# untitled.net
KiCad netlist of a schematic drawn in EAGLE
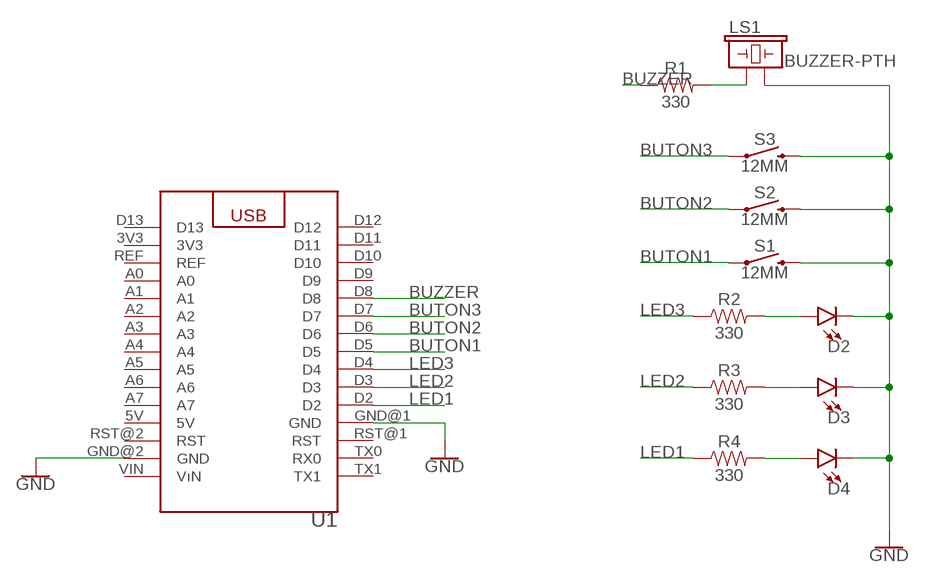
[diagram p0: schematic, sheet 1]

(export (version "E")
  (design (tool "Eeschema 10.0.6"))
  (components
    (comp (ref "D2")
      (value "LED-3MM-NO_SILK")
      (footprint "eagle-import:LED_3MM-NS")
      (libsource (lib "eagle-import") (part "LED-3MM-NO_SILK"))
    )
    (comp (ref "D3")
      (value "LED-3MM-NO_SILK")
      (footprint "eagle-import:LED_3MM-NS")
      (libsource (lib "eagle-import") (part "LED-3MM-NO_SILK"))
    )
    (comp (ref "D4")
      (value "LED-3MM-NO_SILK")
      (footprint "eagle-import:LED_3MM-NS")
      (libsource (lib "eagle-import") (part "LED-3MM-NO_SILK"))
    )
    (comp (ref "LS1")
      (value "BUZZER-PTH")
      (footprint "eagle-import:BUZZER-12MM")
      (libsource (lib "eagle-import") (part "BUZZER-PTH"))
    )
    (comp (ref "R1")
      (value "330")
      (footprint "eagle-import:AXIAL-0.3")
      (libsource (lib "eagle-import") (part "1KOHM-HORIZ-1/4W-5%"))
    )
    (comp (ref "R2")
      (value "330")
      (footprint "eagle-import:AXIAL-0.3")
      (libsource (lib "eagle-import") (part "1KOHM-HORIZ-1/4W-5%"))
    )
    (comp (ref "R3")
      (value "330")
      (footprint "eagle-import:AXIAL-0.3")
      (libsource (lib "eagle-import") (part "1KOHM-HORIZ-1/4W-5%"))
    )
    (comp (ref "R4")
      (value "330")
      (footprint "eagle-import:AXIAL-0.3")
      (libsource (lib "eagle-import") (part "1KOHM-HORIZ-1/4W-5%"))
    )
    (comp (ref "S1")
      (value "12MM")
      (footprint "eagle-import:TACTILE_SWITCH_PTH_12MM")
      (libsource (lib "eagle-import") (part "MOMENTARY-SWITCH-SPST-PTH-12MM"))
    )
    (comp (ref "S2")
      (value "12MM")
      (footprint "eagle-import:TACTILE_SWITCH_PTH_12MM")
      (libsource (lib "eagle-import") (part "MOMENTARY-SWITCH-SPST-PTH-12MM"))
    )
    (comp (ref "S3")
      (value "12MM")
      (footprint "eagle-import:TACTILE_SWITCH_PTH_12MM")
      (libsource (lib "eagle-import") (part "MOMENTARY-SWITCH-SPST-PTH-12MM"))
    )
    (comp (ref "U1")
      (value "ARDUINO_NANO")
      (footprint "eagle-import:ARDUINO_NANO")
      (libsource (lib "eagle-import") (part "ARDUINO_NANO"))
    )
  )
  (nets
    (net (code "1") (name "/BUTON1") (class "Default")
      (node (ref "S1") (pin "1") (pinfunction "1_1") (pintype "passive"))
      (node (ref "U1") (pin "D5") (pinfunction "D5_D5") (pintype "bidirectional"))
    )
    (net (code "2") (name "/BUTON2") (class "Default")
      (node (ref "S2") (pin "1") (pinfunction "1_1") (pintype "passive"))
      (node (ref "U1") (pin "D6") (pinfunction "D6_D6") (pintype "bidirectional"))
    )
    (net (code "3") (name "/BUTON3") (class "Default")
      (node (ref "S3") (pin "1") (pinfunction "1_1") (pintype "passive"))
      (node (ref "U1") (pin "D7") (pinfunction "D7_D7") (pintype "bidirectional"))
    )
    (net (code "4") (name "/BUZZER") (class "Default")
      (node (ref "R1") (pin "P$1") (pinfunction "1_P$1") (pintype "passive"))
      (node (ref "U1") (pin "D8") (pinfunction "D8_D8") (pintype "bidirectional"))
    )
    (net (code "5") (name "/LED1") (class "Default")
      (node (ref "R4") (pin "P$1") (pinfunction "1_P$1") (pintype "passive"))
      (node (ref "U1") (pin "D2") (pinfunction "D2_D2") (pintype "bidirectional"))
    )
    (net (code "6") (name "/LED2") (class "Default")
      (node (ref "R3") (pin "P$1") (pinfunction "1_P$1") (pintype "passive"))
      (node (ref "U1") (pin "D3") (pinfunction "D3_D3") (pintype "bidirectional"))
    )
    (net (code "7") (name "/LED3") (class "Default")
      (node (ref "R2") (pin "P$1") (pinfunction "1_P$1") (pintype "passive"))
      (node (ref "U1") (pin "D4") (pinfunction "D4_D4") (pintype "bidirectional"))
    )
    (net (code "8") (name "GND") (class "Default")
      (node (ref "D2") (pin "K") (pinfunction "C_K") (pintype "passive"))
      (node (ref "D3") (pin "K") (pinfunction "C_K") (pintype "passive"))
      (node (ref "D4") (pin "K") (pinfunction "C_K") (pintype "passive"))
      (node (ref "LS1") (pin "-") (pinfunction "2_-") (pintype "passive"))
      (node (ref "S1") (pin "3") (pinfunction "2_3") (pintype "passive"))
      (node (ref "S2") (pin "3") (pinfunction "2_3") (pintype "passive"))
      (node (ref "S3") (pin "3") (pinfunction "2_3") (pintype "passive"))
      (node (ref "U1") (pin "GND@1") (pinfunction "GND_GND@1") (pintype "bidirectional"))
      (node (ref "U1") (pin "GND@2") (pinfunction "GND_GND@2") (pintype "bidirectional"))
    )
    (net (code "9") (name "Net-(LS1-1)") (class "Default")
      (node (ref "LS1") (pin "+") (pinfunction "1_+") (pintype "passive"))
      (node (ref "R1") (pin "P$2") (pinfunction "2_P$2") (pintype "passive"))
    )
    (net (code "10") (name "Net-(R2-2)") (class "Default")
      (node (ref "D2") (pin "A") (pinfunction "A_A") (pintype "passive"))
      (node (ref "R2") (pin "P$2") (pinfunction "2_P$2") (pintype "passive"))
    )
    (net (code "11") (name "Net-(R3-2)") (class "Default")
      (node (ref "D3") (pin "A") (pinfunction "A_A") (pintype "passive"))
      (node (ref "R3") (pin "P$2") (pinfunction "2_P$2") (pintype "passive"))
    )
    (net (code "12") (name "Net-(R4-2)") (class "Default")
      (node (ref "D4") (pin "A") (pinfunction "A_A") (pintype "passive"))
      (node (ref "R4") (pin "P$2") (pinfunction "2_P$2") (pintype "passive"))
    )
    (net (code "13") (name "unconnected-(U1-Pad3V3)") (class "Default")
      (node (ref "U1") (pin "3V3") (pinfunction "3V3_3V3") (pintype "bidirectional"))
    )
    (net (code "14") (name "unconnected-(U1-Pad5V)") (class "Default")
      (node (ref "U1") (pin "5V") (pinfunction "5V_5V") (pintype "bidirectional"))
    )
    (net (code "15") (name "unconnected-(U1-PadA0)") (class "Default")
      (node (ref "U1") (pin "A0") (pinfunction "A0_A0") (pintype "bidirectional"))
    )
    (net (code "16") (name "unconnected-(U1-PadA1)") (class "Default")
      (node (ref "U1") (pin "A1") (pinfunction "A1_A1") (pintype "bidirectional"))
    )
    (net (code "17") (name "unconnected-(U1-PadA2)") (class "Default")
      (node (ref "U1") (pin "A2") (pinfunction "A2_A2") (pintype "bidirectional"))
    )
    (net (code "18") (name "unconnected-(U1-PadA3)") (class "Default")
      (node (ref "U1") (pin "A3") (pinfunction "A3_A3") (pintype "bidirectional"))
    )
    (net (code "19") (name "unconnected-(U1-PadA4)") (class "Default")
      (node (ref "U1") (pin "A4") (pinfunction "A4_A4") (pintype "bidirectional"))
    )
    (net (code "20") (name "unconnected-(U1-PadA5)") (class "Default")
      (node (ref "U1") (pin "A5") (pinfunction "A5_A5") (pintype "bidirectional"))
    )
    (net (code "21") (name "unconnected-(U1-PadA6)") (class "Default")
      (node (ref "U1") (pin "A6") (pinfunction "A6_A6") (pintype "bidirectional"))
    )
    (net (code "22") (name "unconnected-(U1-PadA7)") (class "Default")
      (node (ref "U1") (pin "A7") (pinfunction "A7_A7") (pintype "bidirectional"))
    )
    (net (code "23") (name "unconnected-(U1-PadD9)") (class "Default")
      (node (ref "U1") (pin "D9") (pinfunction "D9_D9") (pintype "bidirectional"))
    )
    (net (code "24") (name "unconnected-(U1-PadD10)") (class "Default")
      (node (ref "U1") (pin "D10") (pinfunction "D10_D10") (pintype "bidirectional"))
    )
    (net (code "25") (name "unconnected-(U1-PadD11)") (class "Default")
      (node (ref "U1") (pin "D11") (pinfunction "D11_D11") (pintype "bidirectional"))
    )
    (net (code "26") (name "unconnected-(U1-PadD12)") (class "Default")
      (node (ref "U1") (pin "D12") (pinfunction "D12_D12") (pintype "bidirectional"))
    )
    (net (code "27") (name "unconnected-(U1-PadD13)") (class "Default")
      (node (ref "U1") (pin "D13") (pinfunction "D13_D13") (pintype "bidirectional"))
    )
    (net (code "28") (name "unconnected-(U1-PadREF)") (class "Default")
      (node (ref "U1") (pin "REF") (pinfunction "REF_REF") (pintype "bidirectional"))
    )
    (net (code "29") (name "unconnected-(U1-PadTX1)") (class "Default")
      (node (ref "U1") (pin "TX1") (pinfunction "TX1_TX1") (pintype "bidirectional"))
    )
    (net (code "30") (name "unconnected-(U1-RST-PadRST@1)") (class "Default")
      (node (ref "U1") (pin "RST@1") (pinfunction "RST_RST@1") (pintype "bidirectional"))
    )
    (net (code "31") (name "unconnected-(U1-RST-PadRST@2)") (class "Default")
      (node (ref "U1") (pin "RST@2") (pinfunction "RST_RST@2") (pintype "bidirectional"))
    )
    (net (code "32") (name "unconnected-(U1-RX0-PadTX0)") (class "Default")
      (node (ref "U1") (pin "TX0") (pinfunction "RX0_TX0") (pintype "bidirectional"))
    )
    (net (code "33") (name "unconnected-(U1-VıN-PadVIN)") (class "Default")
      (node (ref "U1") (pin "VIN") (pinfunction "VıN_VIN") (pintype "bidirectional"))
    )
  )
)
